# G882B.net
KiCad netlist of a schematic drawn in EAGLE
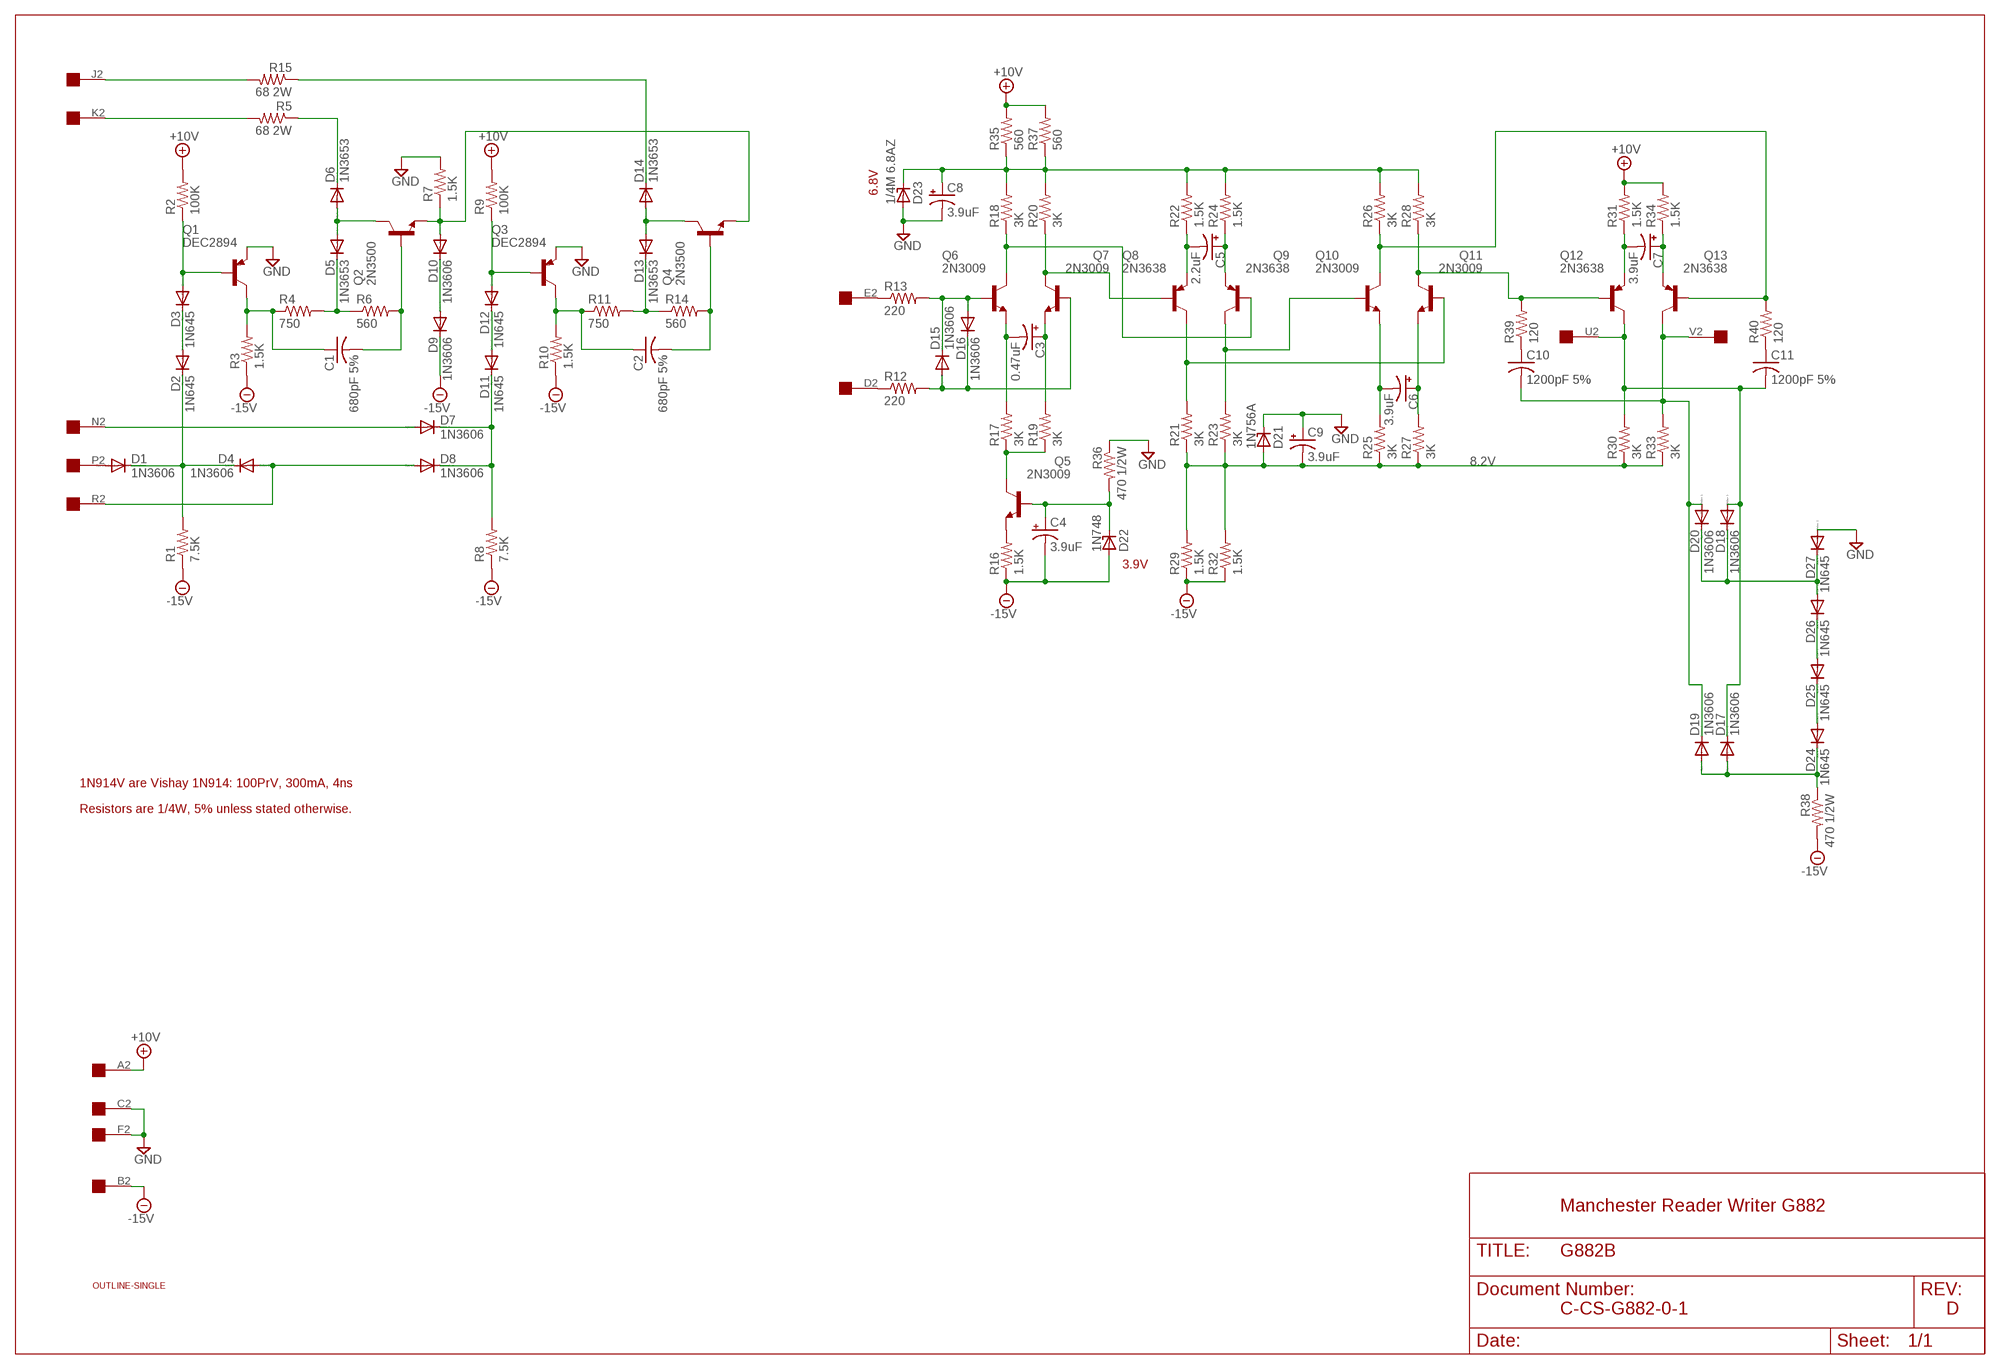
[diagram p0: schematic, sheet 1]

(export (version "E")
  (design (tool "Eeschema 10.0.6"))
  (components
    (comp (ref "C1")
      (value "680pF 5%")
      (footprint "eagle-import:C050-025X075")
      (libsource (lib "eagle-import") (part "C-US050-025X075"))
    )
    (comp (ref "C2")
      (value "680pF 5%")
      (footprint "eagle-import:C050-025X075")
      (libsource (lib "eagle-import") (part "C-US050-025X075"))
    )
    (comp (ref "C3")
      (value "0.47uF")
      (footprint "eagle-import:E12-4")
      (libsource (lib "eagle-import") (part "CPOL-USE12-4AXIAL"))
    )
    (comp (ref "C4")
      (value "3.9uF")
      (footprint "eagle-import:E12-4")
      (libsource (lib "eagle-import") (part "CPOL-USE12-4AXIAL"))
    )
    (comp (ref "C5")
      (value "2.2uF")
      (footprint "eagle-import:E12-4")
      (libsource (lib "eagle-import") (part "CPOL-USE12-4AXIAL"))
    )
    (comp (ref "C6")
      (value "3.9uF")
      (footprint "eagle-import:E12-4")
      (libsource (lib "eagle-import") (part "CPOL-USE12-4AXIAL"))
    )
    (comp (ref "C7")
      (value "3.9uF")
      (footprint "eagle-import:E12-4")
      (libsource (lib "eagle-import") (part "CPOL-USE12-4AXIAL"))
    )
    (comp (ref "C8")
      (value "3.9uF")
      (footprint "eagle-import:E12-4")
      (libsource (lib "eagle-import") (part "CPOL-USE12-4AXIAL"))
    )
    (comp (ref "C9")
      (value "3.9uF")
      (footprint "eagle-import:E12-4")
      (libsource (lib "eagle-import") (part "CPOL-USE12-4AXIAL"))
    )
    (comp (ref "C10")
      (value "1200pF 5%")
      (footprint "eagle-import:C050-025X075")
      (libsource (lib "eagle-import") (part "C-US050-025X075"))
    )
    (comp (ref "C11")
      (value "1200pF 5%")
      (footprint "eagle-import:C050-025X075")
      (libsource (lib "eagle-import") (part "C-US050-025X075"))
    )
    (comp (ref "D1")
      (value "1N3606")
      (footprint "eagle-import:DO35-10")
      (libsource (lib "eagle-import") (part "1N4148DO35-10"))
    )
    (comp (ref "D2")
      (value "1N645")
      (footprint "eagle-import:DO35-10")
      (libsource (lib "eagle-import") (part "1N4148DO35-10"))
    )
    (comp (ref "D3")
      (value "1N645")
      (footprint "eagle-import:DO35-10")
      (libsource (lib "eagle-import") (part "1N4148DO35-10"))
    )
    (comp (ref "D4")
      (value "1N3606")
      (footprint "eagle-import:DO35-10")
      (libsource (lib "eagle-import") (part "1N4148DO35-10"))
    )
    (comp (ref "D5")
      (value "1N3653")
      (footprint "eagle-import:DO35-10")
      (libsource (lib "eagle-import") (part "1N4148DO35-10"))
    )
    (comp (ref "D6")
      (value "1N3653")
      (footprint "eagle-import:DO35-10")
      (libsource (lib "eagle-import") (part "1N4148DO35-10"))
    )
    (comp (ref "D7")
      (value "1N3606")
      (footprint "eagle-import:DO35-10")
      (libsource (lib "eagle-import") (part "1N4148DO35-10"))
    )
    (comp (ref "D8")
      (value "1N3606")
      (footprint "eagle-import:DO35-10")
      (libsource (lib "eagle-import") (part "1N4148DO35-10"))
    )
    (comp (ref "D9")
      (value "1N3606")
      (footprint "eagle-import:DO35-10")
      (libsource (lib "eagle-import") (part "1N4148DO35-10"))
    )
    (comp (ref "D10")
      (value "1N3606")
      (footprint "eagle-import:DO35-10")
      (libsource (lib "eagle-import") (part "1N4148DO35-10"))
    )
    (comp (ref "D11")
      (value "1N645")
      (footprint "eagle-import:DO35-10")
      (libsource (lib "eagle-import") (part "1N4148DO35-10"))
    )
    (comp (ref "D12")
      (value "1N645")
      (footprint "eagle-import:DO35-10")
      (libsource (lib "eagle-import") (part "1N4148DO35-10"))
    )
    (comp (ref "D13")
      (value "1N3653")
      (footprint "eagle-import:DO35-10")
      (libsource (lib "eagle-import") (part "1N4148DO35-10"))
    )
    (comp (ref "D14")
      (value "1N3653")
      (footprint "eagle-import:DO35-10")
      (libsource (lib "eagle-import") (part "1N4148DO35-10"))
    )
    (comp (ref "D15")
      (value "1N3606")
      (footprint "eagle-import:DO35-10")
      (libsource (lib "eagle-import") (part "1N4148DO35-10"))
    )
    (comp (ref "D16")
      (value "1N3606")
      (footprint "eagle-import:DO35-10")
      (libsource (lib "eagle-import") (part "1N4148DO35-10"))
    )
    (comp (ref "D17")
      (value "1N3606")
      (footprint "eagle-import:DO35-10")
      (libsource (lib "eagle-import") (part "1N4148DO35-10"))
    )
    (comp (ref "D18")
      (value "1N3606")
      (footprint "eagle-import:DO35-10")
      (libsource (lib "eagle-import") (part "1N4148DO35-10"))
    )
    (comp (ref "D19")
      (value "1N3606")
      (footprint "eagle-import:DO35-10")
      (libsource (lib "eagle-import") (part "1N4148DO35-10"))
    )
    (comp (ref "D20")
      (value "1N3606")
      (footprint "eagle-import:DO35-10")
      (libsource (lib "eagle-import") (part "1N4148DO35-10"))
    )
    (comp (ref "D21")
      (value "1N756A")
      (footprint "eagle-import:DO35Z10")
      (libsource (lib "eagle-import") (part "ZENER-DIODEDO35Z10"))
    )
    (comp (ref "D22")
      (value "1N748")
      (footprint "eagle-import:DO35Z10")
      (libsource (lib "eagle-import") (part "ZENER-DIODEDO35Z10"))
    )
    (comp (ref "D23")
      (value "1/4M 6.8AZ")
      (footprint "eagle-import:DO35Z10")
      (libsource (lib "eagle-import") (part "ZENER-DIODEDO35Z10"))
    )
    (comp (ref "D24")
      (value "1N645")
      (footprint "eagle-import:DO35-10")
      (libsource (lib "eagle-import") (part "1N4148DO35-10"))
    )
    (comp (ref "D25")
      (value "1N645")
      (footprint "eagle-import:DO35-10")
      (libsource (lib "eagle-import") (part "1N4148DO35-10"))
    )
    (comp (ref "D26")
      (value "1N645")
      (footprint "eagle-import:DO35-10")
      (libsource (lib "eagle-import") (part "1N4148DO35-10"))
    )
    (comp (ref "D27")
      (value "1N645")
      (footprint "eagle-import:DO35-10")
      (libsource (lib "eagle-import") (part "1N4148DO35-10"))
    )
    (comp (ref "Q1")
      (value "DEC2894")
      (footprint "eagle-import:TO39")
      (libsource (lib "eagle-import") (part "2N3635"))
    )
    (comp (ref "Q2")
      (value "2N3500")
      (footprint "eagle-import:TO5")
      (libsource (lib "eagle-import") (part "2N2102"))
    )
    (comp (ref "Q3")
      (value "DEC2894")
      (footprint "eagle-import:TO39")
      (libsource (lib "eagle-import") (part "2N3635"))
    )
    (comp (ref "Q4")
      (value "2N3500")
      (footprint "eagle-import:TO5")
      (libsource (lib "eagle-import") (part "2N2102"))
    )
    (comp (ref "Q5")
      (value "2N3009")
      (footprint "eagle-import:TO5")
      (libsource (lib "eagle-import") (part "2N2102"))
    )
    (comp (ref "Q6")
      (value "2N3009")
      (footprint "eagle-import:TO5")
      (libsource (lib "eagle-import") (part "2N2102"))
    )
    (comp (ref "Q7")
      (value "2N3009")
      (footprint "eagle-import:TO5")
      (libsource (lib "eagle-import") (part "2N2102"))
    )
    (comp (ref "Q8")
      (value "2N3638")
      (footprint "eagle-import:TO39")
      (libsource (lib "eagle-import") (part "2N3635"))
    )
    (comp (ref "Q9")
      (value "2N3638")
      (footprint "eagle-import:TO39")
      (libsource (lib "eagle-import") (part "2N3635"))
    )
    (comp (ref "Q10")
      (value "2N3009")
      (footprint "eagle-import:TO5")
      (libsource (lib "eagle-import") (part "2N2102"))
    )
    (comp (ref "Q11")
      (value "2N3009")
      (footprint "eagle-import:TO5")
      (libsource (lib "eagle-import") (part "2N2102"))
    )
    (comp (ref "Q12")
      (value "2N3638")
      (footprint "eagle-import:TO39")
      (libsource (lib "eagle-import") (part "2N3635"))
    )
    (comp (ref "Q13")
      (value "2N3638")
      (footprint "eagle-import:TO39")
      (libsource (lib "eagle-import") (part "2N3635"))
    )
    (comp (ref "R1")
      (value "7.5K")
      (footprint "eagle-import:0207_10")
      (libsource (lib "eagle-import") (part "R-US_0207/10"))
    )
    (comp (ref "R2")
      (value "100K")
      (footprint "eagle-import:0207_10")
      (libsource (lib "eagle-import") (part "R-US_0207/10"))
    )
    (comp (ref "R3")
      (value "1.5K")
      (footprint "eagle-import:0207_10")
      (libsource (lib "eagle-import") (part "R-US_0207/10"))
    )
    (comp (ref "R4")
      (value "750")
      (footprint "eagle-import:0207_10")
      (libsource (lib "eagle-import") (part "R-US_0207/10"))
    )
    (comp (ref "R5")
      (value "68 2W")
      (footprint "eagle-import:P0817_22")
      (libsource (lib "eagle-import") (part "R-US_0817/22"))
    )
    (comp (ref "R6")
      (value "560")
      (footprint "eagle-import:0207_10")
      (libsource (lib "eagle-import") (part "R-US_0207/10"))
    )
    (comp (ref "R7")
      (value "1.5K")
      (footprint "eagle-import:0207_10")
      (libsource (lib "eagle-import") (part "R-US_0207/10"))
    )
    (comp (ref "R8")
      (value "7.5K")
      (footprint "eagle-import:0207_10")
      (libsource (lib "eagle-import") (part "R-US_0207/10"))
    )
    (comp (ref "R9")
      (value "100K")
      (footprint "eagle-import:0207_10")
      (libsource (lib "eagle-import") (part "R-US_0207/10"))
    )
    (comp (ref "R10")
      (value "1.5K")
      (footprint "eagle-import:0207_10")
      (libsource (lib "eagle-import") (part "R-US_0207/10"))
    )
    (comp (ref "R11")
      (value "750")
      (footprint "eagle-import:0207_10")
      (libsource (lib "eagle-import") (part "R-US_0207/10"))
    )
    (comp (ref "R12")
      (value "220")
      (footprint "eagle-import:0207_10")
      (libsource (lib "eagle-import") (part "R-US_0207/10"))
    )
    (comp (ref "R13")
      (value "220")
      (footprint "eagle-import:0207_10")
      (libsource (lib "eagle-import") (part "R-US_0207/10"))
    )
    (comp (ref "R14")
      (value "560")
      (footprint "eagle-import:0207_10")
      (libsource (lib "eagle-import") (part "R-US_0207/10"))
    )
    (comp (ref "R15")
      (value "68 2W")
      (footprint "eagle-import:P0817_22")
      (libsource (lib "eagle-import") (part "R-US_0817/22"))
    )
    (comp (ref "R16")
      (value "1.5K")
      (footprint "eagle-import:0207_10")
      (libsource (lib "eagle-import") (part "R-US_0207/10"))
    )
    (comp (ref "R17")
      (value "3K")
      (footprint "eagle-import:0207_10")
      (libsource (lib "eagle-import") (part "R-US_0207/10"))
    )
    (comp (ref "R18")
      (value "3K")
      (footprint "eagle-import:0207_10")
      (libsource (lib "eagle-import") (part "R-US_0207/10"))
    )
    (comp (ref "R19")
      (value "3K")
      (footprint "eagle-import:0207_10")
      (libsource (lib "eagle-import") (part "R-US_0207/10"))
    )
    (comp (ref "R20")
      (value "3K")
      (footprint "eagle-import:0207_10")
      (libsource (lib "eagle-import") (part "R-US_0207/10"))
    )
    (comp (ref "R21")
      (value "3K")
      (footprint "eagle-import:0207_10")
      (libsource (lib "eagle-import") (part "R-US_0207/10"))
    )
    (comp (ref "R22")
      (value "1.5K")
      (footprint "eagle-import:0207_10")
      (libsource (lib "eagle-import") (part "R-US_0207/10"))
    )
    (comp (ref "R23")
      (value "3K")
      (footprint "eagle-import:0207_10")
      (libsource (lib "eagle-import") (part "R-US_0207/10"))
    )
    (comp (ref "R24")
      (value "1.5K")
      (footprint "eagle-import:0207_10")
      (libsource (lib "eagle-import") (part "R-US_0207/10"))
    )
    (comp (ref "R25")
      (value "3K")
      (footprint "eagle-import:0207_10")
      (libsource (lib "eagle-import") (part "R-US_0207/10"))
    )
    (comp (ref "R26")
      (value "3K")
      (footprint "eagle-import:0207_10")
      (libsource (lib "eagle-import") (part "R-US_0207/10"))
    )
    (comp (ref "R27")
      (value "3K")
      (footprint "eagle-import:0207_10")
      (libsource (lib "eagle-import") (part "R-US_0207/10"))
    )
    (comp (ref "R28")
      (value "3K")
      (footprint "eagle-import:0207_10")
      (libsource (lib "eagle-import") (part "R-US_0207/10"))
    )
    (comp (ref "R29")
      (value "1.5K")
      (footprint "eagle-import:0207_10")
      (libsource (lib "eagle-import") (part "R-US_0207/10"))
    )
    (comp (ref "R30")
      (value "3K")
      (footprint "eagle-import:0207_10")
      (libsource (lib "eagle-import") (part "R-US_0207/10"))
    )
    (comp (ref "R31")
      (value "1.5K")
      (footprint "eagle-import:0207_10")
      (libsource (lib "eagle-import") (part "R-US_0207/10"))
    )
    (comp (ref "R32")
      (value "1.5K")
      (footprint "eagle-import:0207_10")
      (libsource (lib "eagle-import") (part "R-US_0207/10"))
    )
    (comp (ref "R33")
      (value "3K")
      (footprint "eagle-import:0207_10")
      (libsource (lib "eagle-import") (part "R-US_0207/10"))
    )
    (comp (ref "R34")
      (value "1.5K")
      (footprint "eagle-import:0207_10")
      (libsource (lib "eagle-import") (part "R-US_0207/10"))
    )
    (comp (ref "R35")
      (value "560")
      (footprint "eagle-import:0207_10")
      (libsource (lib "eagle-import") (part "R-US_0207/10"))
    )
    (comp (ref "R36")
      (value "470 1/2W")
      (footprint "eagle-import:0309_12")
      (libsource (lib "eagle-import") (part "R-US_0309/12"))
    )
    (comp (ref "R37")
      (value "560")
      (footprint "eagle-import:0207_10")
      (libsource (lib "eagle-import") (part "R-US_0207/10"))
    )
    (comp (ref "R38")
      (value "470 1/2W")
      (footprint "eagle-import:0309_12")
      (libsource (lib "eagle-import") (part "R-US_0309/12"))
    )
    (comp (ref "R39")
      (value "120")
      (footprint "eagle-import:0207_10")
      (libsource (lib "eagle-import") (part "R-US_0207/10"))
    )
    (comp (ref "R40")
      (value "120")
      (footprint "eagle-import:0207_10")
      (libsource (lib "eagle-import") (part "R-US_0207/10"))
    )
    (comp (ref "U$1")
      (value "OUTLINE-SINGLE")
      (footprint "eagle-import:SINGLE")
      (libsource (lib "eagle-import") (part "OUTLINE-SINGLE"))
    )
    (comp (ref "U$2")
      (value "EDGE-1")
      (footprint "eagle-import:EDGE-CON1")
      (libsource (lib "eagle-import") (part "EDGE-1"))
    )
  )
  (nets
    (net (code "1") (name "+10V") (class "Default")
      (node (ref "R2") (pin "2") (pinfunction "2_2") (pintype "passive"))
      (node (ref "R31") (pin "2") (pinfunction "2_2") (pintype "passive"))
      (node (ref "R34") (pin "2") (pinfunction "2_2") (pintype "passive"))
      (node (ref "R35") (pin "2") (pinfunction "2_2") (pintype "passive"))
      (node (ref "R37") (pin "2") (pinfunction "2_2") (pintype "passive"))
      (node (ref "R9") (pin "2") (pinfunction "2_2") (pintype "passive"))
      (node (ref "U$2") (pin "A2") (pinfunction "1_A2") (pintype "bidirectional"))
    )
    (net (code "2") (name "-15V") (class "Default")
      (node (ref "C4") (pin "-") (pinfunction "-_-") (pintype "passive"))
      (node (ref "D22") (pin "A") (pinfunction "A_A") (pintype "passive"))
      (node (ref "D9") (pin "C") (pinfunction "C_C") (pintype "passive"))
      (node (ref "R1") (pin "1") (pinfunction "1_1") (pintype "passive"))
      (node (ref "R10") (pin "1") (pinfunction "1_1") (pintype "passive"))
      (node (ref "R16") (pin "1") (pinfunction "1_1") (pintype "passive"))
      (node (ref "R29") (pin "1") (pinfunction "1_1") (pintype "passive"))
      (node (ref "R3") (pin "1") (pinfunction "1_1") (pintype "passive"))
      (node (ref "R32") (pin "1") (pinfunction "1_1") (pintype "passive"))
      (node (ref "R38") (pin "2") (pinfunction "2_2") (pintype "passive"))
      (node (ref "R8") (pin "1") (pinfunction "1_1") (pintype "passive"))
      (node (ref "U$2") (pin "B2") (pinfunction "1_B2") (pintype "bidirectional"))
    )
    (net (code "3") (name "/8.2V") (class "Default")
      (node (ref "C9") (pin "-") (pinfunction "-_-") (pintype "passive"))
      (node (ref "D21") (pin "A") (pinfunction "A_A") (pintype "passive"))
      (node (ref "R21") (pin "1") (pinfunction "1_1") (pintype "passive"))
      (node (ref "R23") (pin "1") (pinfunction "1_1") (pintype "passive"))
      (node (ref "R25") (pin "1") (pinfunction "1_1") (pintype "passive"))
      (node (ref "R27") (pin "1") (pinfunction "1_1") (pintype "passive"))
      (node (ref "R29") (pin "2") (pinfunction "2_2") (pintype "passive"))
      (node (ref "R30") (pin "1") (pinfunction "1_1") (pintype "passive"))
      (node (ref "R32") (pin "2") (pinfunction "2_2") (pintype "passive"))
      (node (ref "R33") (pin "1") (pinfunction "1_1") (pintype "passive"))
    )
    (net (code "4") (name "GND") (class "Default")
      (node (ref "C8") (pin "-") (pinfunction "-_-") (pintype "passive"))
      (node (ref "C9") (pin "+") (pinfunction "+_+") (pintype "passive"))
      (node (ref "D21") (pin "C") (pinfunction "C_C") (pintype "passive"))
      (node (ref "D23") (pin "A") (pinfunction "A_A") (pintype "passive"))
      (node (ref "D27") (pin "A") (pinfunction "A_A") (pintype "passive"))
      (node (ref "Q1") (pin "1") (pinfunction "E_1") (pintype "passive"))
      (node (ref "Q3") (pin "1") (pinfunction "E_1") (pintype "passive"))
      (node (ref "R36") (pin "1") (pinfunction "1_1") (pintype "passive"))
      (node (ref "R7") (pin "2") (pinfunction "2_2") (pintype "passive"))
      (node (ref "U$2") (pin "C2") (pinfunction "1_C2") (pintype "bidirectional"))
      (node (ref "U$2") (pin "F2") (pinfunction "1_F2") (pintype "bidirectional"))
    )
    (net (code "5") (name "Net-(C8-Pad+)") (class "Default")
      (node (ref "C8") (pin "+") (pinfunction "+_+") (pintype "passive"))
      (node (ref "D23") (pin "C") (pinfunction "C_C") (pintype "passive"))
      (node (ref "R18") (pin "2") (pinfunction "2_2") (pintype "passive"))
      (node (ref "R20") (pin "2") (pinfunction "2_2") (pintype "passive"))
      (node (ref "R22") (pin "2") (pinfunction "2_2") (pintype "passive"))
      (node (ref "R24") (pin "2") (pinfunction "2_2") (pintype "passive"))
      (node (ref "R26") (pin "2") (pinfunction "2_2") (pintype "passive"))
      (node (ref "R28") (pin "2") (pinfunction "2_2") (pintype "passive"))
      (node (ref "R35") (pin "1") (pinfunction "1_1") (pintype "passive"))
      (node (ref "R37") (pin "1") (pinfunction "1_1") (pintype "passive"))
    )
    (net (code "6") (name "Net-(C10-Pad1)") (class "Default")
      (node (ref "C10") (pin "1") (pinfunction "1_1") (pintype "passive"))
      (node (ref "R39") (pin "1") (pinfunction "1_1") (pintype "passive"))
    )
    (net (code "7") (name "Net-(C11-Pad1)") (class "Default")
      (node (ref "C11") (pin "1") (pinfunction "1_1") (pintype "passive"))
      (node (ref "R40") (pin "1") (pinfunction "1_1") (pintype "passive"))
    )
    (net (code "8") (name "Net-(D1-PadC)") (class "Default")
      (node (ref "D1") (pin "C") (pinfunction "C_C") (pintype "passive"))
      (node (ref "D2") (pin "C") (pinfunction "C_C") (pintype "passive"))
      (node (ref "D4") (pin "C") (pinfunction "C_C") (pintype "passive"))
      (node (ref "R1") (pin "2") (pinfunction "2_2") (pintype "passive"))
    )
    (net (code "9") (name "Net-(D2-PadA)") (class "Default")
      (node (ref "D2") (pin "A") (pinfunction "A_A") (pintype "passive"))
      (node (ref "D3") (pin "C") (pinfunction "C_C") (pintype "passive"))
    )
    (net (code "10") (name "Net-(D5-PadC)") (class "Default")
      (node (ref "D5") (pin "C") (pinfunction "C_C") (pintype "passive"))
      (node (ref "R4") (pin "2") (pinfunction "2_2") (pintype "passive"))
      (node (ref "R6") (pin "1") (pinfunction "1_1") (pintype "passive"))
    )
    (net (code "11") (name "Net-(D6-PadC)") (class "Default")
      (node (ref "D6") (pin "C") (pinfunction "C_C") (pintype "passive"))
      (node (ref "R5") (pin "1") (pinfunction "1_1") (pintype "passive"))
    )
    (net (code "12") (name "Net-(D10-PadC)") (class "Default")
      (node (ref "D10") (pin "C") (pinfunction "C_C") (pintype "passive"))
      (node (ref "D9") (pin "A") (pinfunction "A_A") (pintype "passive"))
    )
    (net (code "13") (name "Net-(D11-PadA)") (class "Default")
      (node (ref "D11") (pin "A") (pinfunction "A_A") (pintype "passive"))
      (node (ref "D12") (pin "C") (pinfunction "C_C") (pintype "passive"))
    )
    (net (code "14") (name "Net-(D11-PadC)") (class "Default")
      (node (ref "D11") (pin "C") (pinfunction "C_C") (pintype "passive"))
      (node (ref "D7") (pin "C") (pinfunction "C_C") (pintype "passive"))
      (node (ref "D8") (pin "C") (pinfunction "C_C") (pintype "passive"))
      (node (ref "R8") (pin "2") (pinfunction "2_2") (pintype "passive"))
    )
    (net (code "15") (name "Net-(D13-PadC)") (class "Default")
      (node (ref "D13") (pin "C") (pinfunction "C_C") (pintype "passive"))
      (node (ref "R11") (pin "2") (pinfunction "2_2") (pintype "passive"))
      (node (ref "R14") (pin "1") (pinfunction "1_1") (pintype "passive"))
    )
    (net (code "16") (name "Net-(D14-PadC)") (class "Default")
      (node (ref "D14") (pin "C") (pinfunction "C_C") (pintype "passive"))
      (node (ref "R15") (pin "1") (pinfunction "1_1") (pintype "passive"))
    )
    (net (code "17") (name "Net-(D17-PadA)") (class "Default")
      (node (ref "D17") (pin "A") (pinfunction "A_A") (pintype "passive"))
      (node (ref "D19") (pin "A") (pinfunction "A_A") (pintype "passive"))
      (node (ref "D24") (pin "C") (pinfunction "C_C") (pintype "passive"))
      (node (ref "R38") (pin "1") (pinfunction "1_1") (pintype "passive"))
    )
    (net (code "18") (name "Net-(D18-PadC)") (class "Default")
      (node (ref "D18") (pin "C") (pinfunction "C_C") (pintype "passive"))
      (node (ref "D20") (pin "C") (pinfunction "C_C") (pintype "passive"))
      (node (ref "D26") (pin "A") (pinfunction "A_A") (pintype "passive"))
      (node (ref "D27") (pin "C") (pinfunction "C_C") (pintype "passive"))
    )
    (net (code "19") (name "Net-(D24-PadA)") (class "Default")
      (node (ref "D24") (pin "A") (pinfunction "A_A") (pintype "passive"))
      (node (ref "D25") (pin "C") (pinfunction "C_C") (pintype "passive"))
    )
    (net (code "20") (name "Net-(D25-PadA)") (class "Default")
      (node (ref "D25") (pin "A") (pinfunction "A_A") (pintype "passive"))
      (node (ref "D26") (pin "C") (pinfunction "C_C") (pintype "passive"))
    )
    (net (code "21") (name "Net-(Q1-B)") (class "Default")
      (node (ref "D3") (pin "A") (pinfunction "A_A") (pintype "passive"))
      (node (ref "Q1") (pin "2") (pinfunction "B_2") (pintype "passive"))
      (node (ref "R2") (pin "1") (pinfunction "1_1") (pintype "passive"))
    )
    (net (code "22") (name "Net-(Q1-C)") (class "Default")
      (node (ref "C1") (pin "1") (pinfunction "1_1") (pintype "passive"))
      (node (ref "Q1") (pin "3") (pinfunction "C_3") (pintype "passive"))
      (node (ref "R3") (pin "2") (pinfunction "2_2") (pintype "passive"))
      (node (ref "R4") (pin "1") (pinfunction "1_1") (pintype "passive"))
    )
    (net (code "23") (name "Net-(Q2-B)") (class "Default")
      (node (ref "C1") (pin "2") (pinfunction "2_2") (pintype "passive"))
      (node (ref "Q2") (pin "2") (pinfunction "B_2") (pintype "passive"))
      (node (ref "R6") (pin "2") (pinfunction "2_2") (pintype "passive"))
    )
    (net (code "24") (name "Net-(Q2-C)") (class "Default")
      (node (ref "D5") (pin "A") (pinfunction "A_A") (pintype "passive"))
      (node (ref "D6") (pin "A") (pinfunction "A_A") (pintype "passive"))
      (node (ref "Q2") (pin "3") (pinfunction "C_3") (pintype "passive"))
    )
    (net (code "25") (name "Net-(Q2-E)") (class "Default")
      (node (ref "D10") (pin "A") (pinfunction "A_A") (pintype "passive"))
      (node (ref "Q2") (pin "1") (pinfunction "E_1") (pintype "passive"))
      (node (ref "Q4") (pin "1") (pinfunction "E_1") (pintype "passive"))
      (node (ref "R7") (pin "1") (pinfunction "1_1") (pintype "passive"))
    )
    (net (code "26") (name "Net-(Q3-B)") (class "Default")
      (node (ref "D12") (pin "A") (pinfunction "A_A") (pintype "passive"))
      (node (ref "Q3") (pin "2") (pinfunction "B_2") (pintype "passive"))
      (node (ref "R9") (pin "1") (pinfunction "1_1") (pintype "passive"))
    )
    (net (code "27") (name "Net-(Q3-C)") (class "Default")
      (node (ref "C2") (pin "1") (pinfunction "1_1") (pintype "passive"))
      (node (ref "Q3") (pin "3") (pinfunction "C_3") (pintype "passive"))
      (node (ref "R10") (pin "2") (pinfunction "2_2") (pintype "passive"))
      (node (ref "R11") (pin "1") (pinfunction "1_1") (pintype "passive"))
    )
    (net (code "28") (name "Net-(Q4-B)") (class "Default")
      (node (ref "C2") (pin "2") (pinfunction "2_2") (pintype "passive"))
      (node (ref "Q4") (pin "2") (pinfunction "B_2") (pintype "passive"))
      (node (ref "R14") (pin "2") (pinfunction "2_2") (pintype "passive"))
    )
    (net (code "29") (name "Net-(Q4-C)") (class "Default")
      (node (ref "D13") (pin "A") (pinfunction "A_A") (pintype "passive"))
      (node (ref "D14") (pin "A") (pinfunction "A_A") (pintype "passive"))
      (node (ref "Q4") (pin "3") (pinfunction "C_3") (pintype "passive"))
    )
    (net (code "30") (name "Net-(Q5-B)") (class "Default")
      (node (ref "C4") (pin "+") (pinfunction "+_+") (pintype "passive"))
      (node (ref "D22") (pin "C") (pinfunction "C_C") (pintype "passive"))
      (node (ref "Q5") (pin "2") (pinfunction "B_2") (pintype "passive"))
      (node (ref "R36") (pin "2") (pinfunction "2_2") (pintype "passive"))
    )
    (net (code "31") (name "Net-(Q5-C)") (class "Default")
      (node (ref "Q5") (pin "3") (pinfunction "C_3") (pintype "passive"))
      (node (ref "R17") (pin "1") (pinfunction "1_1") (pintype "passive"))
      (node (ref "R19") (pin "1") (pinfunction "1_1") (pintype "passive"))
    )
    (net (code "32") (name "Net-(Q5-E)") (class "Default")
      (node (ref "Q5") (pin "1") (pinfunction "E_1") (pintype "passive"))
      (node (ref "R16") (pin "2") (pinfunction "2_2") (pintype "passive"))
    )
    (net (code "33") (name "Net-(Q6-B)") (class "Default")
      (node (ref "D15") (pin "C") (pinfunction "C_C") (pintype "passive"))
      (node (ref "D16") (pin "A") (pinfunction "A_A") (pintype "passive"))
      (node (ref "Q6") (pin "2") (pinfunction "B_2") (pintype "passive"))
      (node (ref "R13") (pin "2") (pinfunction "2_2") (pintype "passive"))
    )
    (net (code "34") (name "Net-(Q6-C)") (class "Default")
      (node (ref "Q6") (pin "3") (pinfunction "C_3") (pintype "passive"))
      (node (ref "Q9") (pin "2") (pinfunction "B_2") (pintype "passive"))
      (node (ref "R18") (pin "1") (pinfunction "1_1") (pintype "passive"))
    )
    (net (code "35") (name "Net-(Q6-E)") (class "Default")
      (node (ref "C3") (pin "-") (pinfunction "-_-") (pintype "passive"))
      (node (ref "Q6") (pin "1") (pinfunction "E_1") (pintype "passive"))
      (node (ref "R17") (pin "2") (pinfunction "2_2") (pintype "passive"))
    )
    (net (code "36") (name "Net-(Q7-B)") (class "Default")
      (node (ref "D15") (pin "A") (pinfunction "A_A") (pintype "passive"))
      (node (ref "D16") (pin "C") (pinfunction "C_C") (pintype "passive"))
      (node (ref "Q7") (pin "2") (pinfunction "B_2") (pintype "passive"))
      (node (ref "R12") (pin "2") (pinfunction "2_2") (pintype "passive"))
    )
    (net (code "37") (name "Net-(Q7-C)") (class "Default")
      (node (ref "Q7") (pin "3") (pinfunction "C_3") (pintype "passive"))
      (node (ref "Q8") (pin "2") (pinfunction "B_2") (pintype "passive"))
      (node (ref "R20") (pin "1") (pinfunction "1_1") (pintype "passive"))
    )
    (net (code "38") (name "Net-(Q7-E)") (class "Default")
      (node (ref "C3") (pin "+") (pinfunction "+_+") (pintype "passive"))
      (node (ref "Q7") (pin "1") (pinfunction "E_1") (pintype "passive"))
      (node (ref "R19") (pin "2") (pinfunction "2_2") (pintype "passive"))
    )
    (net (code "39") (name "Net-(Q8-E)") (class "Default")
      (node (ref "C5") (pin "-") (pinfunction "-_-") (pintype "passive"))
      (node (ref "Q8") (pin "1") (pinfunction "E_1") (pintype "passive"))
      (node (ref "R22") (pin "1") (pinfunction "1_1") (pintype "passive"))
    )
    (net (code "40") (name "Net-(Q9-E)") (class "Default")
      (node (ref "C5") (pin "+") (pinfunction "+_+") (pintype "passive"))
      (node (ref "Q9") (pin "1") (pinfunction "E_1") (pintype "passive"))
      (node (ref "R24") (pin "1") (pinfunction "1_1") (pintype "passive"))
    )
    (net (code "41") (name "Net-(Q10-B)") (class "Default")
      (node (ref "Q10") (pin "2") (pinfunction "B_2") (pintype "passive"))
      (node (ref "Q9") (pin "3") (pinfunction "C_3") (pintype "passive"))
      (node (ref "R23") (pin "2") (pinfunction "2_2") (pintype "passive"))
    )
    (net (code "42") (name "Net-(Q10-C)") (class "Default")
      (node (ref "Q10") (pin "3") (pinfunction "C_3") (pintype "passive"))
      (node (ref "Q13") (pin "2") (pinfunction "B_2") (pintype "passive"))
      (node (ref "R26") (pin "1") (pinfunction "1_1") (pintype "passive"))
      (node (ref "R40") (pin "2") (pinfunction "2_2") (pintype "passive"))
    )
    (net (code "43") (name "Net-(Q10-E)") (class "Default")
      (node (ref "C6") (pin "-") (pinfunction "-_-") (pintype "passive"))
      (node (ref "Q10") (pin "1") (pinfunction "E_1") (pintype "passive"))
      (node (ref "R25") (pin "2") (pinfunction "2_2") (pintype "passive"))
    )
    (net (code "44") (name "Net-(Q11-B)") (class "Default")
      (node (ref "Q11") (pin "2") (pinfunction "B_2") (pintype "passive"))
      (node (ref "Q8") (pin "3") (pinfunction "C_3") (pintype "passive"))
      (node (ref "R21") (pin "2") (pinfunction "2_2") (pintype "passive"))
    )
    (net (code "45") (name "Net-(Q11-C)") (class "Default")
      (node (ref "Q11") (pin "3") (pinfunction "C_3") (pintype "passive"))
      (node (ref "Q12") (pin "2") (pinfunction "B_2") (pintype "passive"))
      (node (ref "R28") (pin "1") (pinfunction "1_1") (pintype "passive"))
      (node (ref "R39") (pin "2") (pinfunction "2_2") (pintype "passive"))
    )
    (net (code "46") (name "Net-(Q11-E)") (class "Default")
      (node (ref "C6") (pin "+") (pinfunction "+_+") (pintype "passive"))
      (node (ref "Q11") (pin "1") (pinfunction "E_1") (pintype "passive"))
      (node (ref "R27") (pin "2") (pinfunction "2_2") (pintype "passive"))
    )
    (net (code "47") (name "Net-(Q12-C)") (class "Default")
      (node (ref "C11") (pin "2") (pinfunction "2_2") (pintype "passive"))
      (node (ref "D17") (pin "C") (pinfunction "C_C") (pintype "passive"))
      (node (ref "D18") (pin "A") (pinfunction "A_A") (pintype "passive"))
      (node (ref "Q12") (pin "3") (pinfunction "C_3") (pintype "passive"))
      (node (ref "R30") (pin "2") (pinfunction "2_2") (pintype "passive"))
      (node (ref "U$2") (pin "U2") (pinfunction "1_U2") (pintype "bidirectional"))
    )
    (net (code "48") (name "Net-(Q12-E)") (class "Default")
      (node (ref "C7") (pin "-") (pinfunction "-_-") (pintype "passive"))
      (node (ref "Q12") (pin "1") (pinfunction "E_1") (pintype "passive"))
      (node (ref "R31") (pin "1") (pinfunction "1_1") (pintype "passive"))
    )
    (net (code "49") (name "Net-(Q13-C)") (class "Default")
      (node (ref "C10") (pin "2") (pinfunction "2_2") (pintype "passive"))
      (node (ref "D19") (pin "C") (pinfunction "C_C") (pintype "passive"))
      (node (ref "D20") (pin "A") (pinfunction "A_A") (pintype "passive"))
      (node (ref "Q13") (pin "3") (pinfunction "C_3") (pintype "passive"))
      (node (ref "R33") (pin "2") (pinfunction "2_2") (pintype "passive"))
      (node (ref "U$2") (pin "V2") (pinfunction "1_V2") (pintype "bidirectional"))
    )
    (net (code "50") (name "Net-(Q13-E)") (class "Default")
      (node (ref "C7") (pin "+") (pinfunction "+_+") (pintype "passive"))
      (node (ref "Q13") (pin "1") (pinfunction "E_1") (pintype "passive"))
      (node (ref "R34") (pin "1") (pinfunction "1_1") (pintype "passive"))
    )
    (net (code "51") (name "Net-(U$2D-1)") (class "Default")
      (node (ref "R12") (pin "1") (pinfunction "1_1") (pintype "passive"))
      (node (ref "U$2") (pin "D2") (pinfunction "1_D2") (pintype "bidirectional"))
    )
    (net (code "52") (name "Net-(U$2E-1)") (class "Default")
      (node (ref "R13") (pin "1") (pinfunction "1_1") (pintype "passive"))
      (node (ref "U$2") (pin "E2") (pinfunction "1_E2") (pintype "bidirectional"))
    )
    (net (code "53") (name "Net-(U$2H-1)") (class "Default")
      (node (ref "R15") (pin "2") (pinfunction "2_2") (pintype "passive"))
      (node (ref "U$2") (pin "J2") (pinfunction "1_J2") (pintype "bidirectional"))
    )
    (net (code "54") (name "Net-(U$2I-1)") (class "Default")
      (node (ref "R5") (pin "2") (pinfunction "2_2") (pintype "passive"))
      (node (ref "U$2") (pin "K2") (pinfunction "1_K2") (pintype "bidirectional"))
    )
    (net (code "55") (name "Net-(U$2L-1)") (class "Default")
      (node (ref "D7") (pin "A") (pinfunction "A_A") (pintype "passive"))
      (node (ref "U$2") (pin "N2") (pinfunction "1_N2") (pintype "bidirectional"))
    )
    (net (code "56") (name "Net-(U$2M-1)") (class "Default")
      (node (ref "D1") (pin "A") (pinfunction "A_A") (pintype "passive"))
      (node (ref "U$2") (pin "P2") (pinfunction "1_P2") (pintype "bidirectional"))
    )
    (net (code "57") (name "Net-(U$2N-1)") (class "Default")
      (node (ref "D4") (pin "A") (pinfunction "A_A") (pintype "passive"))
      (node (ref "D8") (pin "A") (pinfunction "A_A") (pintype "passive"))
      (node (ref "U$2") (pin "R2") (pinfunction "1_R2") (pintype "bidirectional"))
    )
  )
)
